# CH32V002D4U.net
KiCad netlist of a schematic drawn in Altium Designer
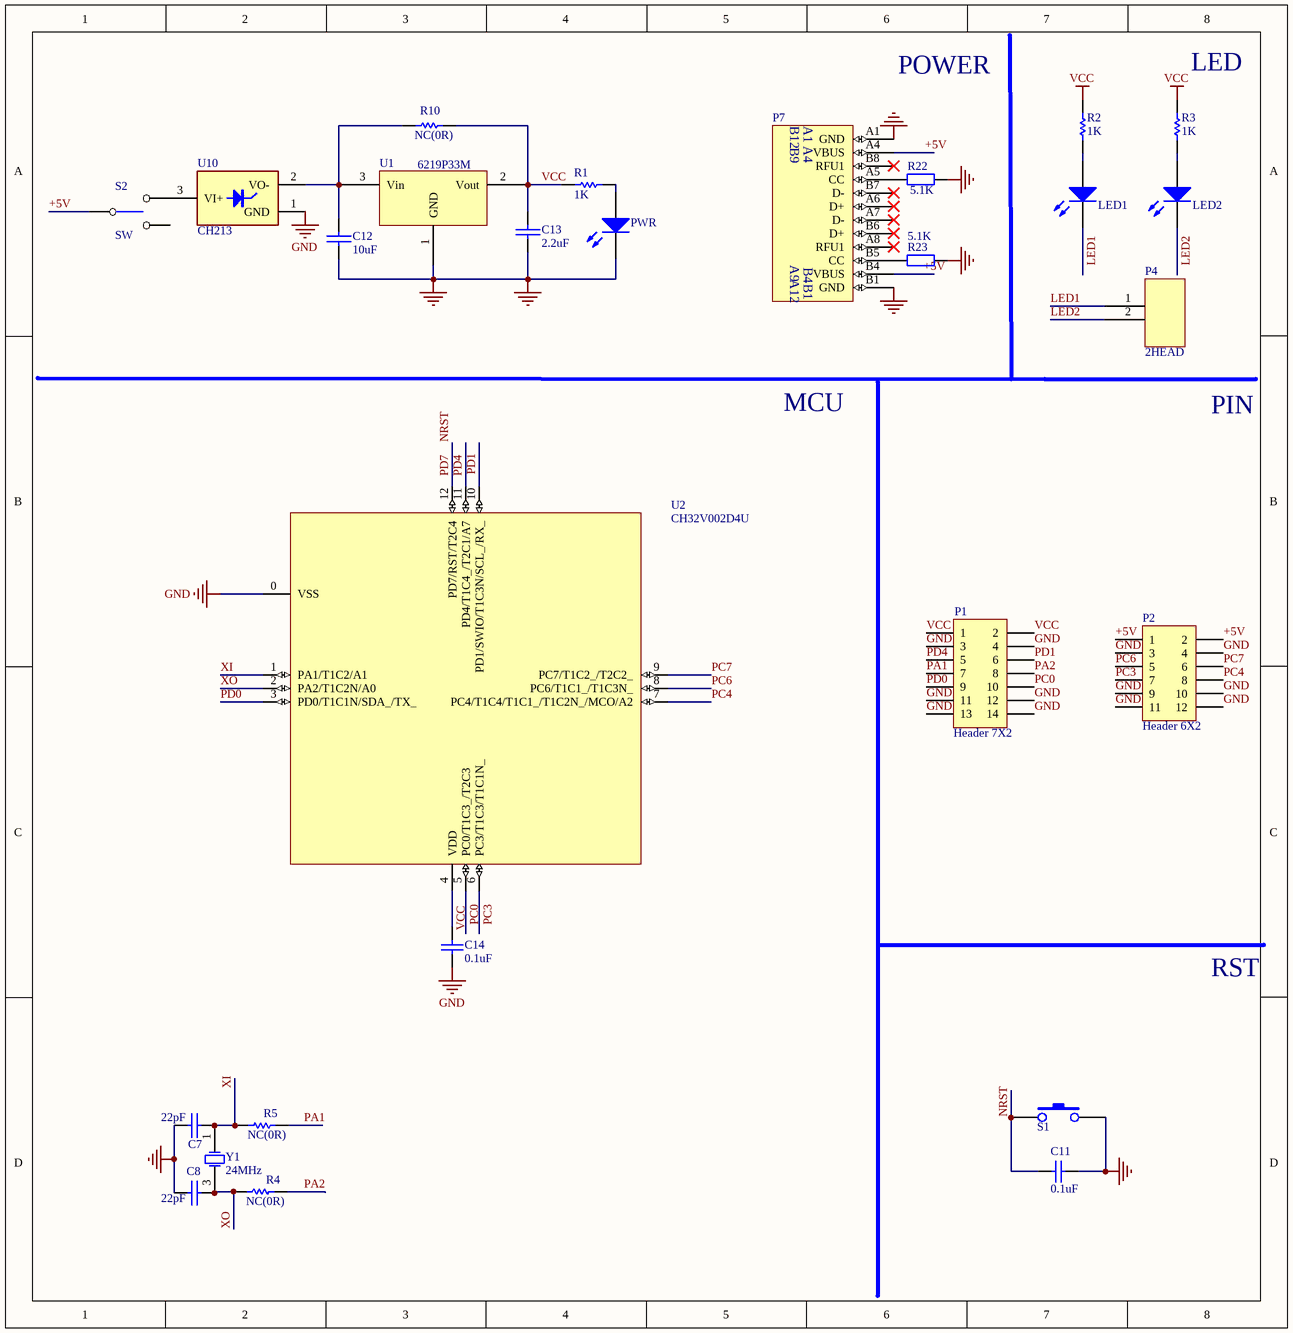
[diagram p0: CH32V002D4U.SchDoc]

(export (version "E")
  (design (tool "Eeschema 10.0.6"))
  (components
    (comp (ref "C7")
      (value "22pF")
      (footprint "0402_C")
      (description "Capacitor")
      (libsource (lib "*") (part "CAP"))
    )
    (comp (ref "C8")
      (value "22pF")
      (footprint "0402_C")
      (description "Capacitor")
      (libsource (lib "*") (part "CAP"))
    )
    (comp (ref "C11")
      (value "0.1uF")
      (footprint "0402_C")
      (description "Capacitor")
      (fields (field (name "PUBLISHER") "Altium Limited"))
      (libsource (lib "*") (part "Cap"))
    )
    (comp (ref "C12")
      (value "10uF")
      (footprint "0603_C")
      (description "Capacitor")
      (libsource (lib "wch_sch_others") (part "CAP"))
    )
    (comp (ref "C13")
      (value "2.2uF")
      (footprint "0402_C")
      (description "Capacitor")
      (libsource (lib "wch_sch_others") (part "CAP"))
    )
    (comp (ref "C14")
      (value "0.1uF")
      (footprint "0603_C")
      (description "Capacitor")
      (fields (field (name "PUBLISHER") "Altium Limited"))
      (libsource (lib "*") (part "Cap"))
    )
    (comp (ref "LED1")
      (value "LED1   blue")
      (footprint "0603+")
      (description "Typical INFRARED GaAs LED")
      (fields (field (name "PUBLISHER") "Altium Limited"))
      (libsource (lib "") (part "LED0_1"))
    )
    (comp (ref "LED2")
      (value "LED2  blue")
      (footprint "0603+")
      (description "Typical INFRARED GaAs LED")
      (fields (field (name "PUBLISHER") "Altium Limited"))
      (libsource (lib "") (part "LED0_1"))
    )
    (comp (ref "P1")
      (value "Header 7X2")
      (footprint "HDR2X7")
      (description "Header, 7-Pin, Dual row")
      (fields (field (name "PUBLISHER") "Altium Limited"))
      (libsource (lib "Miscellaneous Connectors") (part "Header 7X2"))
    )
    (comp (ref "P2")
      (value "Header 6X2")
      (footprint "HDR2X6")
      (description "Header, 6-Pin, Dual row")
      (fields (field (name "PUBLISHER") "Altium Limited"))
      (libsource (lib "Miscellaneous Connectors") (part "Header 6X2"))
    )
    (comp (ref "P4") (value "2HEAD") (footprint "SIP2-2.54mm") (libsource (lib "*") (part "2HEAD")))
    (comp (ref "P7")
      (value "TYPE-C")
      (footprint "TYPE-C-Receptacle-2.0")
      (libsource (lib "*") (part "TYPE-C1"))
    )
    (comp (ref "PWR")
      (value "POWER  red")
      (footprint "0603+")
      (description "Typical INFRARED GaAs LED")
      (fields (field (name "PUBLISHER") "Altium Limited"))
      (libsource (lib "*") (part "LED0"))
    )
    (comp (ref "R1")
      (value "1K")
      (footprint "0402")
      (description "Semiconductor Resistor")
      (fields (field (name "PUBLISHER") "Altium Limited"))
      (libsource (lib "*") (part "Res Semi"))
    )
    (comp (ref "R2")
      (value "1K")
      (footprint "0402")
      (description "Semiconductor Resistor")
      (fields (field (name "PUBLISHER") "Altium Limited"))
      (libsource (lib "*") (part "Res Semi"))
    )
    (comp (ref "R3")
      (value "1K")
      (footprint "0402")
      (description "Semiconductor Resistor")
      (fields (field (name "PUBLISHER") "Altium Limited"))
      (libsource (lib "*") (part "Res Semi"))
    )
    (comp (ref "R4")
      (value "NC(0R)")
      (footprint "0402")
      (description "Semiconductor Resistor")
      (fields (field (name "Comment") "0R") (field (name "PUBLISHER") "Altium Limited"))
      (libsource (lib "*") (part "Res Semi"))
    )
    (comp (ref "R5")
      (value "NC(0R)")
      (footprint "0402")
      (description "Semiconductor Resistor")
      (fields (field (name "Comment") "0R") (field (name "PUBLISHER") "Altium Limited"))
      (libsource (lib "*") (part "Res Semi"))
    )
    (comp (ref "R10")
      (value "NC(0R)")
      (footprint "0402")
      (description "Semiconductor Resistor")
      (fields (field (name "Comment") "0R") (field (name "PUBLISHER") "Altium Limited"))
      (libsource (lib "*") (part "Res Semi"))
    )
    (comp (ref "R22")
      (value "5.1K")
      (footprint "0402")
      (description "Resistor")
      (libsource (lib "Miscellaneous Devices") (part "Res2"))
    )
    (comp (ref "R23")
      (value "5.1K")
      (footprint "0402")
      (description "Resistor")
      (libsource (lib "Miscellaneous Devices") (part "Res2"))
    )
    (comp (ref "S1") (value "NRST") (footprint "SMD_6.1x3.65x2.5mm-KEY") (libsource (lib "*") (part "KEY")))
    (comp (ref "S2") (value "SW") (footprint "SW1") (libsource (lib "*") (part "SW")))
    (comp (ref "U1")
      (value "6219P33M")
      (footprint "SOT-23")
      (libsource (lib "wch_sch_others") (part "6219P33M"))
    )
    (comp (ref "U2")
      (value "CH32V002D4U")
      (footprint "QFN12_2X2")
      (description "RISC-V MCU, 48MHz, ADC/UART/I2C")
      (libsource (lib "DHXXXSCH") (part "CH32V002D4U6"))
    )
    (comp (ref "U10")
      (value "CH213")
      (footprint "SOT-23-3")
      (description "Ideal Diode 5V*1A")
      (libsource (lib "CHXXX") (part "CH213E"))
    )
    (comp (ref "Y1")
      (value "24MHz")
      (footprint "XT3225")
      (description "Crystal Oscillator")
      (fields (field (name "PUBLISHER") "Altium Limited"))
      (libsource (lib "*") (part "XTAL"))
    )
  )
  (nets
    (net (code "1") (name "/+5V") (class "Default")
      (node (ref "P2") (pin "1") (pinfunction "1_1") (pintype "passive"))
      (node (ref "P2") (pin "2") (pinfunction "2_2") (pintype "passive"))
      (node (ref "P7") (pin "A4") (pinfunction "VBUS_A4") (pintype "bidirectional"))
      (node (ref "P7") (pin "B4") (pinfunction "VBUS_B4") (pintype "bidirectional"))
      (node (ref "S2") (pin "1") (pinfunction "1_1") (pintype "passive"))
    )
    (net (code "2") (name "/LED1") (class "Default")
      (node (ref "LED1") (pin "2") (pinfunction "K_2") (pintype "passive"))
      (node (ref "P4") (pin "1") (pintype "passive"))
    )
    (net (code "3") (name "/LED2") (class "Default")
      (node (ref "LED2") (pin "2") (pinfunction "K_2") (pintype "passive"))
      (node (ref "P4") (pin "2") (pintype "passive"))
    )
    (net (code "4") (name "/NRST") (class "Default")
      (node (ref "C11") (pin "2") (pinfunction "2_2") (pintype "passive"))
      (node (ref "S1") (pin "1") (pinfunction "1_1") (pintype "passive"))
      (node (ref "U2") (pin "12") (pinfunction "PD7/RST/T2C4_12") (pintype "bidirectional"))
    )
    (net (code "5") (name "/PA1") (class "Default")
      (node (ref "P1") (pin "7") (pinfunction "7_7") (pintype "passive"))
      (node (ref "R5") (pin "2") (pinfunction "2_2") (pintype "passive"))
    )
    (net (code "6") (name "/PA2") (class "Default")
      (node (ref "P1") (pin "8") (pinfunction "8_8") (pintype "passive"))
      (node (ref "R4") (pin "2") (pinfunction "2_2") (pintype "passive"))
    )
    (net (code "7") (name "/PC0") (class "Default")
      (node (ref "P1") (pin "10") (pinfunction "10_10") (pintype "passive"))
      (node (ref "U2") (pin "5") (pinfunction "PC0/T1C3_/T2C3_5") (pintype "bidirectional"))
    )
    (net (code "8") (name "/PC3") (class "Default")
      (node (ref "P2") (pin "7") (pinfunction "7_7") (pintype "passive"))
      (node (ref "U2") (pin "6") (pinfunction "PC3/T1C3/T1C1N__6") (pintype "bidirectional"))
    )
    (net (code "9") (name "/PC4") (class "Default")
      (node (ref "P2") (pin "8") (pinfunction "8_8") (pintype "passive"))
      (node (ref "U2") (pin "7") (pinfunction "PC4/T1C4/T1C1_/T1C2N_/MCO/A2_7") (pintype "bidirectional"))
    )
    (net (code "10") (name "/PC6") (class "Default")
      (node (ref "P2") (pin "5") (pinfunction "5_5") (pintype "passive"))
      (node (ref "U2") (pin "8") (pinfunction "PC6/T1C1_/T1C3N__8") (pintype "bidirectional"))
    )
    (net (code "11") (name "/PC7") (class "Default")
      (node (ref "P2") (pin "6") (pinfunction "6_6") (pintype "passive"))
      (node (ref "U2") (pin "9") (pinfunction "PC7/T1C2_/T2C2__9") (pintype "bidirectional"))
    )
    (net (code "12") (name "/PD0") (class "Default")
      (node (ref "P1") (pin "9") (pinfunction "9_9") (pintype "passive"))
      (node (ref "U2") (pin "3") (pinfunction "PD0/T1C1N/SDA_/TX__3") (pintype "bidirectional"))
    )
    (net (code "13") (name "/PD1") (class "Default")
      (node (ref "P1") (pin "6") (pinfunction "6_6") (pintype "passive"))
      (node (ref "U2") (pin "10") (pinfunction "PD1/SWIO/T1C3N/SCL_/RX__10") (pintype "bidirectional"))
    )
    (net (code "14") (name "/PD4") (class "Default")
      (node (ref "P1") (pin "5") (pinfunction "5_5") (pintype "passive"))
      (node (ref "U2") (pin "11") (pinfunction "PD4/T1C4_/T2C1/A7_11") (pintype "bidirectional"))
    )
    (net (code "15") (name "/XI") (class "Default")
      (node (ref "C7") (pin "2") (pinfunction "2_2") (pintype "passive"))
      (node (ref "R5") (pin "1") (pinfunction "1_1") (pintype "passive"))
      (node (ref "U2") (pin "1") (pinfunction "PA1/T1C2/A1_1") (pintype "bidirectional"))
      (node (ref "Y1") (pin "1") (pinfunction "OSC1_1") (pintype "passive"))
    )
    (net (code "16") (name "/XO") (class "Default")
      (node (ref "C8") (pin "2") (pinfunction "2_2") (pintype "passive"))
      (node (ref "R4") (pin "1") (pinfunction "1_1") (pintype "passive"))
      (node (ref "U2") (pin "2") (pinfunction "PA2/T1C2N/A0_2") (pintype "bidirectional"))
      (node (ref "Y1") (pin "3") (pinfunction "OSC2_3") (pintype "passive"))
    )
    (net (code "17") (name "GND") (class "Default")
      (node (ref "C11") (pin "1") (pinfunction "1_1") (pintype "passive"))
      (node (ref "C12") (pin "2") (pinfunction "2_2") (pintype "passive"))
      (node (ref "C13") (pin "1") (pinfunction "1_1") (pintype "passive"))
      (node (ref "C14") (pin "2") (pinfunction "2_2") (pintype "passive"))
      (node (ref "C7") (pin "1") (pinfunction "1_1") (pintype "passive"))
      (node (ref "C8") (pin "1") (pinfunction "1_1") (pintype "passive"))
      (node (ref "P1") (pin "11") (pinfunction "11_11") (pintype "passive"))
      (node (ref "P1") (pin "12") (pinfunction "12_12") (pintype "passive"))
      (node (ref "P1") (pin "13") (pinfunction "13_13") (pintype "passive"))
      (node (ref "P1") (pin "14") (pinfunction "14_14") (pintype "passive"))
      (node (ref "P1") (pin "3") (pinfunction "3_3") (pintype "passive"))
      (node (ref "P1") (pin "4") (pinfunction "4_4") (pintype "passive"))
      (node (ref "P2") (pin "10") (pinfunction "10_10") (pintype "passive"))
      (node (ref "P2") (pin "11") (pinfunction "11_11") (pintype "passive"))
      (node (ref "P2") (pin "12") (pinfunction "12_12") (pintype "passive"))
      (node (ref "P2") (pin "3") (pinfunction "3_3") (pintype "passive"))
      (node (ref "P2") (pin "4") (pinfunction "4_4") (pintype "passive"))
      (node (ref "P2") (pin "9") (pinfunction "9_9") (pintype "passive"))
      (node (ref "P7") (pin "A1") (pinfunction "GND_A1") (pintype "bidirectional"))
      (node (ref "P7") (pin "B1") (pinfunction "GND_B1") (pintype "bidirectional"))
      (node (ref "PWR") (pin "2") (pinfunction "K_2") (pintype "passive"))
      (node (ref "R22") (pin "2") (pinfunction "2_2") (pintype "passive"))
      (node (ref "R23") (pin "2") (pinfunction "2_2") (pintype "passive"))
      (node (ref "S1") (pin "2") (pinfunction "2_2") (pintype "passive"))
      (node (ref "U1") (pin "1") (pinfunction "GND_1") (pintype "passive"))
      (node (ref "U10") (pin "1") (pinfunction "GND_1") (pintype "power_in"))
      (node (ref "U2") (pin "0") (pinfunction "VSS_0") (pintype "power_in"))
    )
    (net (code "18") (name "Net-(LED1-A)") (class "Default")
      (node (ref "LED1") (pin "1") (pinfunction "A_1") (pintype "passive"))
      (node (ref "R2") (pin "2") (pinfunction "2_2") (pintype "passive"))
    )
    (net (code "19") (name "Net-(LED2-A)") (class "Default")
      (node (ref "LED2") (pin "1") (pinfunction "A_1") (pintype "passive"))
      (node (ref "R3") (pin "2") (pinfunction "2_2") (pintype "passive"))
    )
    (net (code "20") (name "Net-(P7-CC-PadA5)") (class "Default")
      (node (ref "P7") (pin "A5") (pinfunction "CC_A5") (pintype "bidirectional"))
      (node (ref "R22") (pin "1") (pinfunction "1_1") (pintype "passive"))
    )
    (net (code "21") (name "Net-(P7-CC-PadB5)") (class "Default")
      (node (ref "P7") (pin "B5") (pinfunction "CC_B5") (pintype "bidirectional"))
      (node (ref "R23") (pin "1") (pinfunction "1_1") (pintype "passive"))
    )
    (net (code "22") (name "Net-(PWR-A)") (class "Default")
      (node (ref "PWR") (pin "1") (pinfunction "A_1") (pintype "passive"))
      (node (ref "R1") (pin "1") (pinfunction "1_1") (pintype "passive"))
    )
    (net (code "23") (name "Net-(U1-Vin)") (class "Default")
      (node (ref "C12") (pin "1") (pinfunction "1_1") (pintype "passive"))
      (node (ref "R10") (pin "1") (pinfunction "1_1") (pintype "passive"))
      (node (ref "U1") (pin "3") (pinfunction "Vin_3") (pintype "passive"))
      (node (ref "U10") (pin "2") (pinfunction "VO-_2") (pintype "power_in"))
    )
    (net (code "24") (name "Net-(U10-VI+)") (class "Default")
      (node (ref "S2") (pin "3") (pinfunction "3_3") (pintype "passive"))
      (node (ref "U10") (pin "3") (pinfunction "VI+_3") (pintype "power_in"))
    )
    (net (code "25") (name "VCC") (class "Default")
      (node (ref "C13") (pin "2") (pinfunction "2_2") (pintype "passive"))
      (node (ref "C14") (pin "1") (pinfunction "1_1") (pintype "passive"))
      (node (ref "P1") (pin "1") (pinfunction "1_1") (pintype "passive"))
      (node (ref "P1") (pin "2") (pinfunction "2_2") (pintype "passive"))
      (node (ref "R1") (pin "2") (pinfunction "2_2") (pintype "passive"))
      (node (ref "R10") (pin "2") (pinfunction "2_2") (pintype "passive"))
      (node (ref "R2") (pin "1") (pinfunction "1_1") (pintype "passive"))
      (node (ref "R3") (pin "1") (pinfunction "1_1") (pintype "passive"))
      (node (ref "U1") (pin "2") (pinfunction "Vout_2") (pintype "passive"))
      (node (ref "U2") (pin "4") (pinfunction "VDD_4") (pintype "power_in"))
    )
    (net (code "26") (name "unconnected-(P7-D+-PadA6)") (class "Default")
      (node (ref "P7") (pin "A6") (pinfunction "D+_A6") (pintype "bidirectional+no_connect"))
    )
    (net (code "27") (name "unconnected-(P7-D+-PadB6)") (class "Default")
      (node (ref "P7") (pin "B6") (pinfunction "D+_B6") (pintype "bidirectional+no_connect"))
    )
    (net (code "28") (name "unconnected-(P7-D--PadA7)") (class "Default")
      (node (ref "P7") (pin "A7") (pinfunction "D-_A7") (pintype "bidirectional+no_connect"))
    )
    (net (code "29") (name "unconnected-(P7-D--PadB7)") (class "Default")
      (node (ref "P7") (pin "B7") (pinfunction "D-_B7") (pintype "bidirectional+no_connect"))
    )
    (net (code "30") (name "unconnected-(P7-RFU1-PadA8)") (class "Default")
      (node (ref "P7") (pin "A8") (pinfunction "RFU1_A8") (pintype "bidirectional+no_connect"))
    )
    (net (code "31") (name "unconnected-(P7-RFU1-PadB8)") (class "Default")
      (node (ref "P7") (pin "B8") (pinfunction "RFU1_B8") (pintype "bidirectional+no_connect"))
    )
    (net (code "32") (name "unconnected-(S2-Pad2)") (class "Default")
      (node (ref "S2") (pin "2") (pinfunction "2_2") (pintype "passive"))
    )
  )
)
